# OSSIICBNew.net
KiCad netlist of a schematic drawn in EAGLE
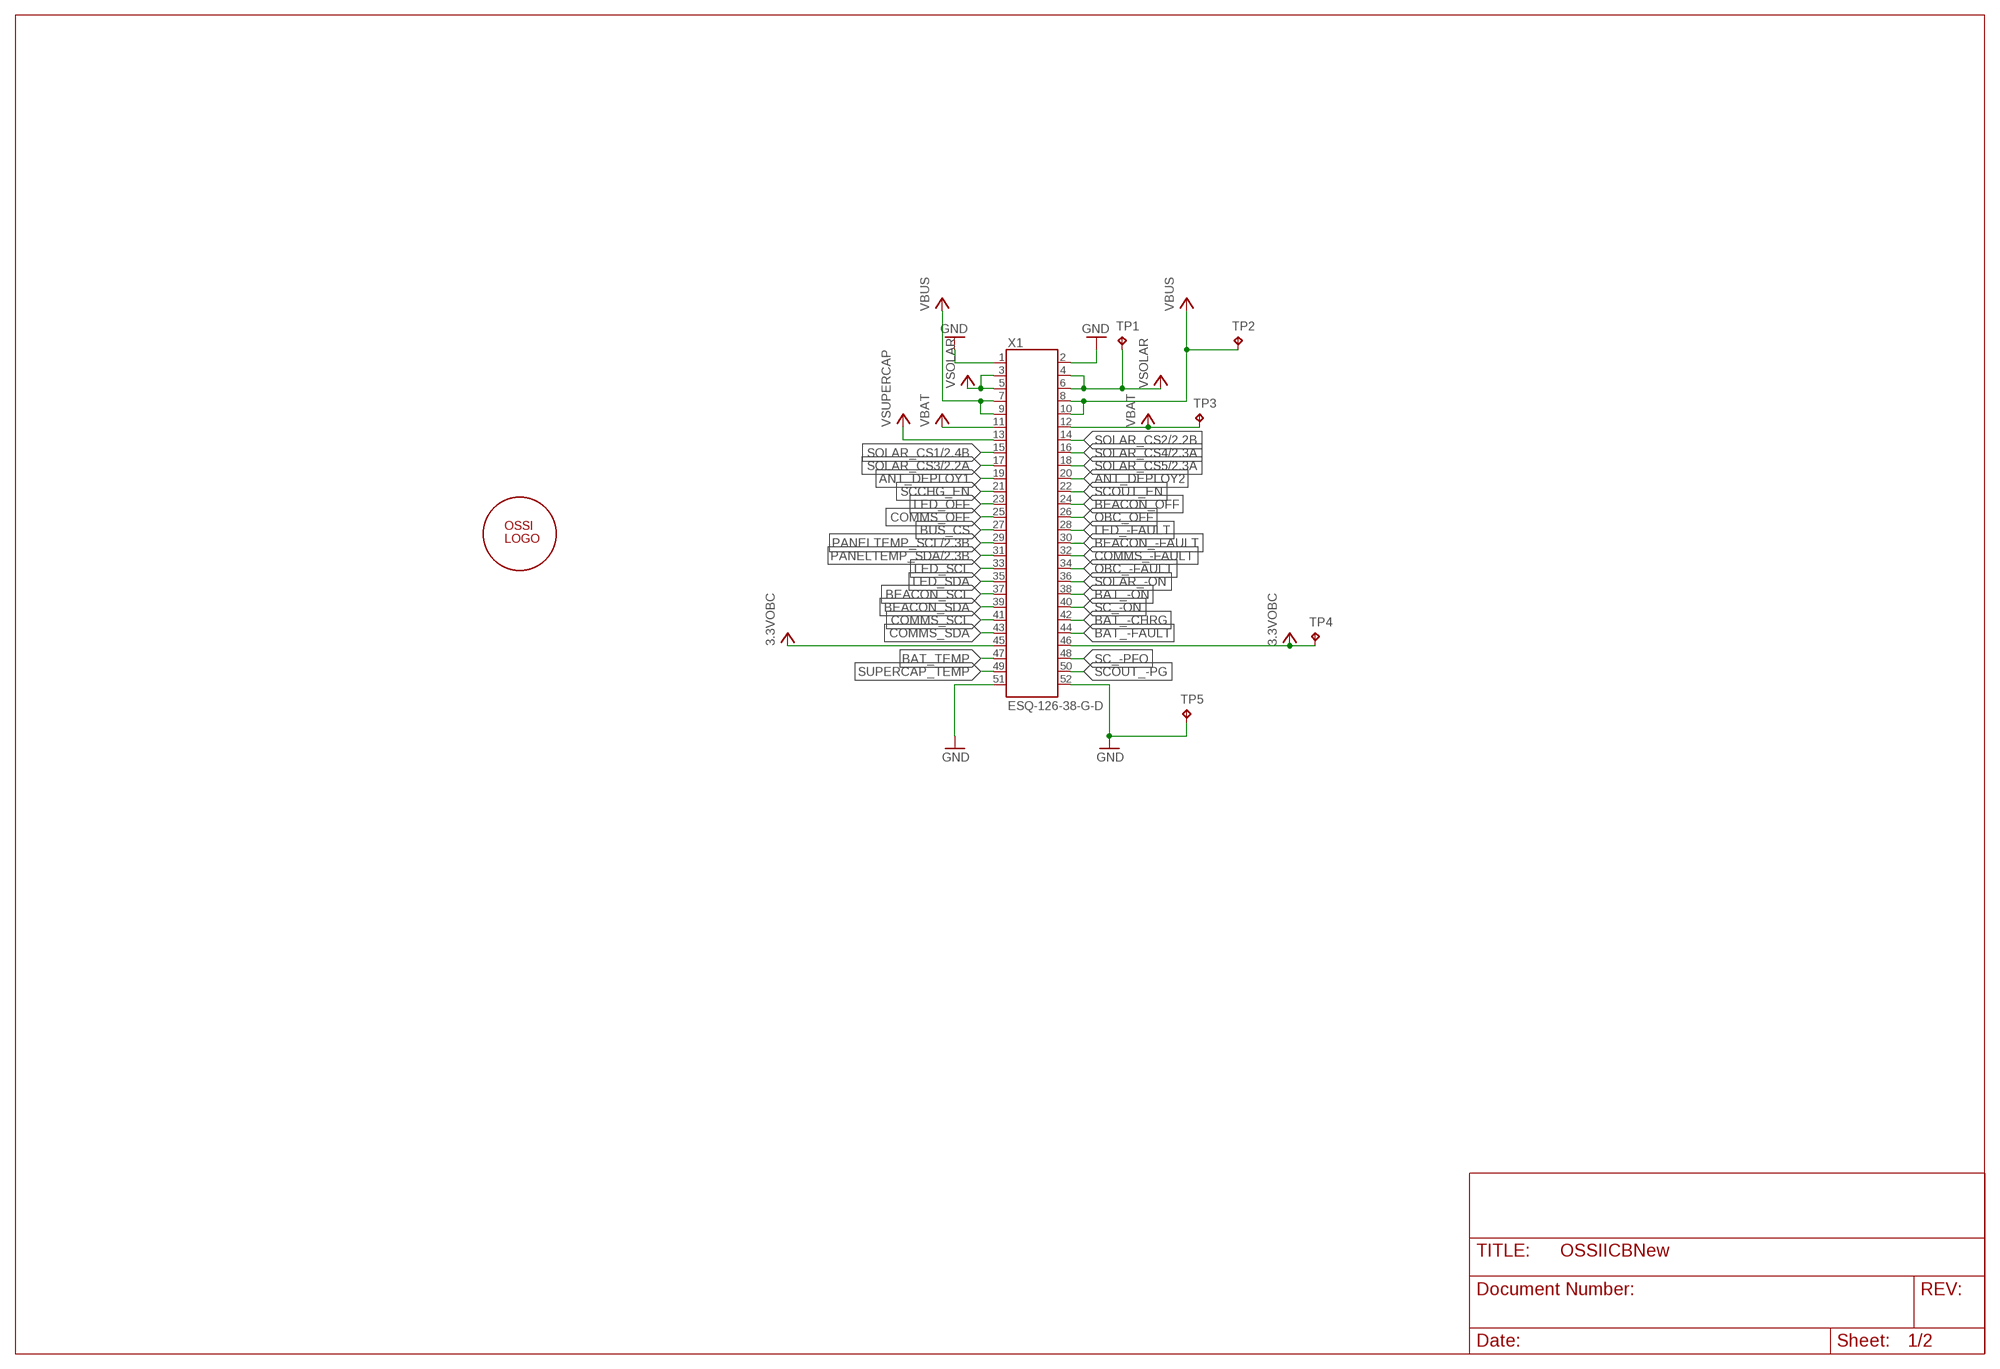
[diagram p0: schematic, sheet 1]
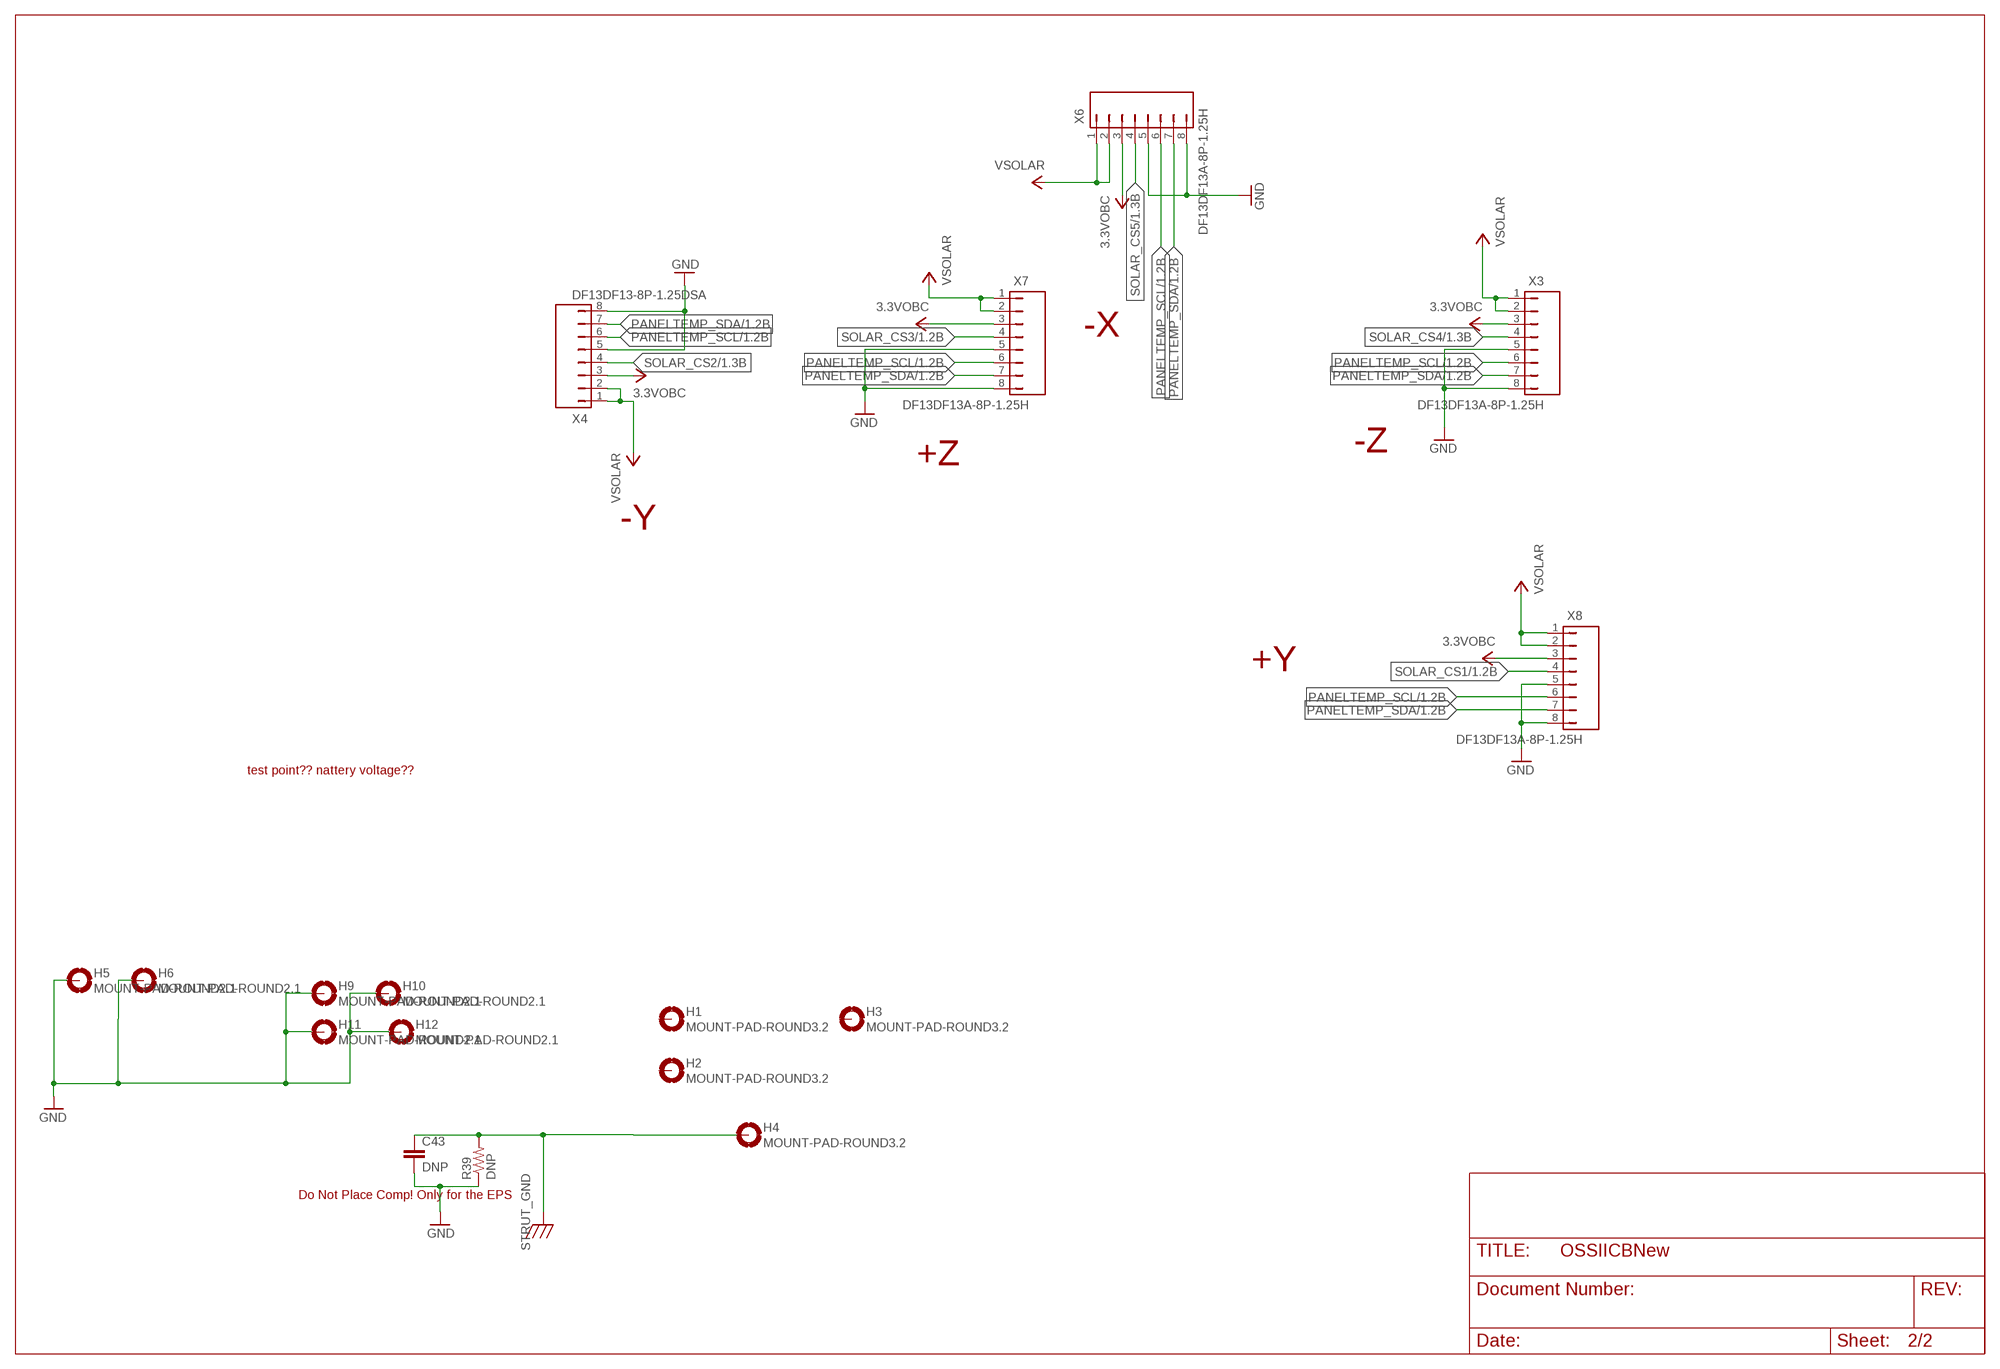
[diagram p1: schematic, sheet 2]

(export (version "E")
  (design (tool "Eeschema 10.0.6"))
  (components
    (comp (ref "TP1")
      (value "TP")
      (footprint "eagle-import:TP-13")
      (libsource (lib "eagle-import") (part "TP"))
    )
    (comp (ref "TP2")
      (value "TP")
      (footprint "eagle-import:TP-13")
      (libsource (lib "eagle-import") (part "TP"))
    )
    (comp (ref "TP3")
      (value "TP")
      (footprint "eagle-import:TP-13")
      (libsource (lib "eagle-import") (part "TP"))
    )
    (comp (ref "TP4")
      (value "TP")
      (footprint "eagle-import:TP-13")
      (libsource (lib "eagle-import") (part "TP"))
    )
    (comp (ref "TP5")
      (value "TP")
      (footprint "eagle-import:TP-13")
      (libsource (lib "eagle-import") (part "TP"))
    )
    (comp (ref "U$1")
      (value "OSSILOGO-10")
      (footprint "eagle-import:OSSILOGO1010")
      (libsource (lib "eagle-import") (part "OSSILOGO-10"))
    )
    (comp (ref "X1")
      (value "ESQ-126-38-G-D")
      (footprint "eagle-import:ESQ-126-XX-X-D")
      (libsource (lib "eagle-import") (part "ESQ-126-38-G-D"))
    )
    (comp (ref "C43")
      (value "DNP")
      (footprint "eagle-import:C0805(2012)")
      (libsource (lib "eagle-import") (part "C0805(2012)"))
    )
    (comp (ref "H1")
      (value "MOUNT-PAD-ROUND3.2")
      (footprint "eagle-import:3.2-PAD-ROUND")
      (libsource (lib "eagle-import") (part "MOUNT-PAD-ROUND3.2"))
    )
    (comp (ref "H2")
      (value "MOUNT-PAD-ROUND3.2")
      (footprint "eagle-import:3.2-PAD-ROUND")
      (libsource (lib "eagle-import") (part "MOUNT-PAD-ROUND3.2"))
    )
    (comp (ref "H3")
      (value "MOUNT-PAD-ROUND3.2")
      (footprint "eagle-import:3.2-PAD-ROUND")
      (libsource (lib "eagle-import") (part "MOUNT-PAD-ROUND3.2"))
    )
    (comp (ref "H4")
      (value "MOUNT-PAD-ROUND3.2")
      (footprint "eagle-import:3.2-PAD-ROUND")
      (libsource (lib "eagle-import") (part "MOUNT-PAD-ROUND3.2"))
    )
    (comp (ref "H5")
      (value "MOUNT-PAD-ROUND2.1")
      (footprint "eagle-import:2.1-PAD-ROUND")
      (libsource (lib "eagle-import") (part "MOUNT-PAD-ROUND2.1"))
    )
    (comp (ref "H6")
      (value "MOUNT-PAD-ROUND2.1")
      (footprint "eagle-import:2.1-PAD-ROUND")
      (libsource (lib "eagle-import") (part "MOUNT-PAD-ROUND2.1"))
    )
    (comp (ref "H9")
      (value "MOUNT-PAD-ROUND2.1")
      (footprint "eagle-import:2.1-PAD-ROUND")
      (libsource (lib "eagle-import") (part "MOUNT-PAD-ROUND2.1"))
    )
    (comp (ref "H10")
      (value "MOUNT-PAD-ROUND2.1")
      (footprint "eagle-import:2.1-PAD-ROUND")
      (libsource (lib "eagle-import") (part "MOUNT-PAD-ROUND2.1"))
    )
    (comp (ref "H11")
      (value "MOUNT-PAD-ROUND2.1")
      (footprint "eagle-import:2.1-PAD-ROUND")
      (libsource (lib "eagle-import") (part "MOUNT-PAD-ROUND2.1"))
    )
    (comp (ref "H12")
      (value "MOUNT-PAD-ROUND2.1")
      (footprint "eagle-import:2.1-PAD-ROUND")
      (libsource (lib "eagle-import") (part "MOUNT-PAD-ROUND2.1"))
    )
    (comp (ref "R39")
      (value "DNP")
      (footprint "eagle-import:WSL1206")
      (libsource (lib "eagle-import") (part "RWSL1206"))
    )
    (comp (ref "X3")
      (value "DF13DF13A-8P-1.25H")
      (footprint "eagle-import:DF13A-8P")
      (libsource (lib "eagle-import") (part "DF13DF13A-8P-1.25H"))
    )
    (comp (ref "X4")
      (value "DF13DF13-8P-1.25DSA")
      (footprint "eagle-import:DF13-8P-1.25DSA")
      (libsource (lib "eagle-import") (part "DF13DF13-8P-1.25DSA"))
    )
    (comp (ref "X6")
      (value "DF13DF13A-8P-1.25H")
      (footprint "eagle-import:DF13A-8P")
      (libsource (lib "eagle-import") (part "DF13DF13A-8P-1.25H"))
    )
    (comp (ref "X7")
      (value "DF13DF13A-8P-1.25H")
      (footprint "eagle-import:DF13A-8P")
      (libsource (lib "eagle-import") (part "DF13DF13A-8P-1.25H"))
    )
    (comp (ref "X8")
      (value "DF13DF13A-8P-1.25H")
      (footprint "eagle-import:DF13A-8P")
      (libsource (lib "eagle-import") (part "DF13DF13A-8P-1.25H"))
    )
  )
  (nets
    (net (code "1") (name "3.3VOBC") (class "Default")
      (node (ref "TP4") (pin "TP") (pinfunction "TP_TP") (pintype "input"))
      (node (ref "X1") (pin "45") (pinfunction "45_45") (pintype "bidirectional"))
      (node (ref "X1") (pin "46") (pinfunction "46_46") (pintype "bidirectional"))
      (node (ref "X3") (pin "3") (pinfunction "3_3") (pintype "passive"))
      (node (ref "X4") (pin "3") (pinfunction "3_3") (pintype "passive"))
      (node (ref "X6") (pin "3") (pinfunction "3_3") (pintype "passive"))
      (node (ref "X7") (pin "3") (pinfunction "3_3") (pintype "passive"))
      (node (ref "X8") (pin "3") (pinfunction "3_3") (pintype "passive"))
    )
    (net (code "2") (name "ANT_DEPLOY1") (class "Default")
      (node (ref "X1") (pin "19") (pinfunction "19_19") (pintype "bidirectional"))
    )
    (net (code "3") (name "ANT_DEPLOY2") (class "Default")
      (node (ref "X1") (pin "20") (pinfunction "20_20") (pintype "bidirectional"))
    )
    (net (code "4") (name "BAT_-CHRG") (class "Default")
      (node (ref "X1") (pin "42") (pinfunction "42_42") (pintype "bidirectional"))
    )
    (net (code "5") (name "BAT_-FAULT") (class "Default")
      (node (ref "X1") (pin "44") (pinfunction "44_44") (pintype "bidirectional"))
    )
    (net (code "6") (name "BAT_-ON") (class "Default")
      (node (ref "X1") (pin "38") (pinfunction "38_38") (pintype "bidirectional"))
    )
    (net (code "7") (name "BAT_TEMP") (class "Default")
      (node (ref "X1") (pin "47") (pinfunction "47_47") (pintype "bidirectional"))
    )
    (net (code "8") (name "BEACON_-FAULT") (class "Default")
      (node (ref "X1") (pin "30") (pinfunction "30_30") (pintype "bidirectional"))
    )
    (net (code "9") (name "BEACON_OFF") (class "Default")
      (node (ref "X1") (pin "24") (pinfunction "24_24") (pintype "bidirectional"))
    )
    (net (code "10") (name "BEACON_SCL") (class "Default")
      (node (ref "X1") (pin "37") (pinfunction "37_37") (pintype "bidirectional"))
    )
    (net (code "11") (name "BEACON_SDA") (class "Default")
      (node (ref "X1") (pin "39") (pinfunction "39_39") (pintype "bidirectional"))
    )
    (net (code "12") (name "BUS_CS") (class "Default")
      (node (ref "X1") (pin "27") (pinfunction "27_27") (pintype "bidirectional"))
    )
    (net (code "13") (name "COMMS_-FAULT") (class "Default")
      (node (ref "X1") (pin "32") (pinfunction "32_32") (pintype "bidirectional"))
    )
    (net (code "14") (name "COMMS_OFF") (class "Default")
      (node (ref "X1") (pin "25") (pinfunction "25_25") (pintype "bidirectional"))
    )
    (net (code "15") (name "COMMS_SCL") (class "Default")
      (node (ref "X1") (pin "41") (pinfunction "41_41") (pintype "bidirectional"))
    )
    (net (code "16") (name "COMMS_SDA") (class "Default")
      (node (ref "X1") (pin "43") (pinfunction "43_43") (pintype "bidirectional"))
    )
    (net (code "17") (name "GND") (class "Default")
      (node (ref "C43") (pin "2") (pinfunction "2_2") (pintype "passive"))
      (node (ref "H10") (pin "B3,2") (pinfunction "MOUNT_B3,2") (pintype "passive"))
      (node (ref "H11") (pin "B3,2") (pinfunction "MOUNT_B3,2") (pintype "passive"))
      (node (ref "H12") (pin "B3,2") (pinfunction "MOUNT_B3,2") (pintype "passive"))
      (node (ref "H5") (pin "B3,2") (pinfunction "MOUNT_B3,2") (pintype "passive"))
      (node (ref "H6") (pin "B3,2") (pinfunction "MOUNT_B3,2") (pintype "passive"))
      (node (ref "H9") (pin "B3,2") (pinfunction "MOUNT_B3,2") (pintype "passive"))
      (node (ref "R39") (pin "P$1") (pinfunction "1_P$1") (pintype "passive"))
      (node (ref "TP5") (pin "TP") (pinfunction "TP_TP") (pintype "input"))
      (node (ref "X1") (pin "1") (pinfunction "1_1") (pintype "bidirectional"))
      (node (ref "X1") (pin "2") (pinfunction "2_2") (pintype "bidirectional"))
      (node (ref "X1") (pin "51") (pinfunction "51_51") (pintype "bidirectional"))
      (node (ref "X1") (pin "52") (pinfunction "52_52") (pintype "bidirectional"))
      (node (ref "X3") (pin "5") (pinfunction "5_5") (pintype "passive"))
      (node (ref "X3") (pin "8") (pinfunction "8_8") (pintype "passive"))
      (node (ref "X4") (pin "5") (pinfunction "5_5") (pintype "passive"))
      (node (ref "X4") (pin "8") (pinfunction "8_8") (pintype "passive"))
      (node (ref "X6") (pin "5") (pinfunction "5_5") (pintype "passive"))
      (node (ref "X6") (pin "8") (pinfunction "8_8") (pintype "passive"))
      (node (ref "X7") (pin "5") (pinfunction "5_5") (pintype "passive"))
      (node (ref "X7") (pin "8") (pinfunction "8_8") (pintype "passive"))
      (node (ref "X8") (pin "5") (pinfunction "5_5") (pintype "passive"))
      (node (ref "X8") (pin "8") (pinfunction "8_8") (pintype "passive"))
    )
    (net (code "18") (name "LED_-FAULT") (class "Default")
      (node (ref "X1") (pin "28") (pinfunction "28_28") (pintype "bidirectional"))
    )
    (net (code "19") (name "LED_OFF") (class "Default")
      (node (ref "X1") (pin "23") (pinfunction "23_23") (pintype "bidirectional"))
    )
    (net (code "20") (name "LED_SCL") (class "Default")
      (node (ref "X1") (pin "33") (pinfunction "33_33") (pintype "bidirectional"))
    )
    (net (code "21") (name "LED_SDA") (class "Default")
      (node (ref "X1") (pin "35") (pinfunction "35_35") (pintype "bidirectional"))
    )
    (net (code "22") (name "OBC_-FAULT") (class "Default")
      (node (ref "X1") (pin "34") (pinfunction "34_34") (pintype "bidirectional"))
    )
    (net (code "23") (name "OBC_OFF") (class "Default")
      (node (ref "X1") (pin "26") (pinfunction "26_26") (pintype "bidirectional"))
    )
    (net (code "24") (name "PANELTEMP_SCL") (class "Default")
      (node (ref "X1") (pin "29") (pinfunction "29_29") (pintype "bidirectional"))
      (node (ref "X3") (pin "6") (pinfunction "6_6") (pintype "passive"))
      (node (ref "X4") (pin "6") (pinfunction "6_6") (pintype "passive"))
      (node (ref "X6") (pin "6") (pinfunction "6_6") (pintype "passive"))
      (node (ref "X7") (pin "6") (pinfunction "6_6") (pintype "passive"))
      (node (ref "X8") (pin "6") (pinfunction "6_6") (pintype "passive"))
    )
    (net (code "25") (name "PANELTEMP_SDA") (class "Default")
      (node (ref "X1") (pin "31") (pinfunction "31_31") (pintype "bidirectional"))
      (node (ref "X3") (pin "7") (pinfunction "7_7") (pintype "passive"))
      (node (ref "X4") (pin "7") (pinfunction "7_7") (pintype "passive"))
      (node (ref "X6") (pin "7") (pinfunction "7_7") (pintype "passive"))
      (node (ref "X7") (pin "7") (pinfunction "7_7") (pintype "passive"))
      (node (ref "X8") (pin "7") (pinfunction "7_7") (pintype "passive"))
    )
    (net (code "26") (name "SCCHG_EN") (class "Default")
      (node (ref "X1") (pin "21") (pinfunction "21_21") (pintype "bidirectional"))
    )
    (net (code "27") (name "SCOUT_-PG") (class "Default")
      (node (ref "X1") (pin "50") (pinfunction "50_50") (pintype "bidirectional"))
    )
    (net (code "28") (name "SCOUT_EN") (class "Default")
      (node (ref "X1") (pin "22") (pinfunction "22_22") (pintype "bidirectional"))
    )
    (net (code "29") (name "SC_-ON") (class "Default")
      (node (ref "X1") (pin "40") (pinfunction "40_40") (pintype "bidirectional"))
    )
    (net (code "30") (name "SC_-PFO") (class "Default")
      (node (ref "X1") (pin "48") (pinfunction "48_48") (pintype "bidirectional"))
    )
    (net (code "31") (name "SOLAR_-ON") (class "Default")
      (node (ref "X1") (pin "36") (pinfunction "36_36") (pintype "bidirectional"))
    )
    (net (code "32") (name "SOLAR_CS1") (class "Default")
      (node (ref "X1") (pin "15") (pinfunction "15_15") (pintype "bidirectional"))
      (node (ref "X8") (pin "4") (pinfunction "4_4") (pintype "passive"))
    )
    (net (code "33") (name "SOLAR_CS2") (class "Default")
      (node (ref "X1") (pin "14") (pinfunction "14_14") (pintype "bidirectional"))
      (node (ref "X4") (pin "4") (pinfunction "4_4") (pintype "passive"))
    )
    (net (code "34") (name "SOLAR_CS3") (class "Default")
      (node (ref "X1") (pin "17") (pinfunction "17_17") (pintype "bidirectional"))
      (node (ref "X7") (pin "4") (pinfunction "4_4") (pintype "passive"))
    )
    (net (code "35") (name "SOLAR_CS4") (class "Default")
      (node (ref "X1") (pin "16") (pinfunction "16_16") (pintype "bidirectional"))
      (node (ref "X3") (pin "4") (pinfunction "4_4") (pintype "passive"))
    )
    (net (code "36") (name "SOLAR_CS5") (class "Default")
      (node (ref "X1") (pin "18") (pinfunction "18_18") (pintype "bidirectional"))
      (node (ref "X6") (pin "4") (pinfunction "4_4") (pintype "passive"))
    )
    (net (code "37") (name "STRUT_GND") (class "Default")
      (node (ref "C43") (pin "1") (pinfunction "1_1") (pintype "passive"))
      (node (ref "H4") (pin "B3,2") (pinfunction "MOUNT_B3,2") (pintype "passive"))
      (node (ref "R39") (pin "P$2") (pinfunction "2_P$2") (pintype "passive"))
    )
    (net (code "38") (name "SUPERCAP_TEMP") (class "Default")
      (node (ref "X1") (pin "49") (pinfunction "49_49") (pintype "bidirectional"))
    )
    (net (code "39") (name "VBAT") (class "Default")
      (node (ref "TP3") (pin "TP") (pinfunction "TP_TP") (pintype "input"))
      (node (ref "X1") (pin "11") (pinfunction "11_11") (pintype "bidirectional"))
      (node (ref "X1") (pin "12") (pinfunction "12_12") (pintype "bidirectional"))
    )
    (net (code "40") (name "VBUS") (class "Default")
      (node (ref "TP2") (pin "TP") (pinfunction "TP_TP") (pintype "input"))
      (node (ref "X1") (pin "10") (pinfunction "10_10") (pintype "bidirectional"))
      (node (ref "X1") (pin "7") (pinfunction "7_7") (pintype "bidirectional"))
      (node (ref "X1") (pin "8") (pinfunction "8_8") (pintype "bidirectional"))
      (node (ref "X1") (pin "9") (pinfunction "9_9") (pintype "bidirectional"))
    )
    (net (code "41") (name "VSOLAR") (class "Default")
      (node (ref "TP1") (pin "TP") (pinfunction "TP_TP") (pintype "input"))
      (node (ref "X1") (pin "3") (pinfunction "3_3") (pintype "bidirectional"))
      (node (ref "X1") (pin "4") (pinfunction "4_4") (pintype "bidirectional"))
      (node (ref "X1") (pin "5") (pinfunction "5_5") (pintype "bidirectional"))
      (node (ref "X1") (pin "6") (pinfunction "6_6") (pintype "bidirectional"))
      (node (ref "X3") (pin "1") (pinfunction "1_1") (pintype "passive"))
      (node (ref "X3") (pin "2") (pinfunction "2_2") (pintype "passive"))
      (node (ref "X4") (pin "1") (pinfunction "1_1") (pintype "passive"))
      (node (ref "X4") (pin "2") (pinfunction "2_2") (pintype "passive"))
      (node (ref "X6") (pin "1") (pinfunction "1_1") (pintype "passive"))
      (node (ref "X6") (pin "2") (pinfunction "2_2") (pintype "passive"))
      (node (ref "X7") (pin "1") (pinfunction "1_1") (pintype "passive"))
      (node (ref "X7") (pin "2") (pinfunction "2_2") (pintype "passive"))
      (node (ref "X8") (pin "1") (pinfunction "1_1") (pintype "passive"))
      (node (ref "X8") (pin "2") (pinfunction "2_2") (pintype "passive"))
    )
    (net (code "42") (name "VSUPERCAP") (class "Default")
      (node (ref "X1") (pin "13") (pinfunction "13_13") (pintype "bidirectional"))
    )
    (net (code "43") (name "unconnected-(H1-MOUNT-PadB3,2)") (class "Default")
      (node (ref "H1") (pin "B3,2") (pinfunction "MOUNT_B3,2") (pintype "passive"))
    )
    (net (code "44") (name "unconnected-(H2-MOUNT-PadB3,2)") (class "Default")
      (node (ref "H2") (pin "B3,2") (pinfunction "MOUNT_B3,2") (pintype "passive"))
    )
    (net (code "45") (name "unconnected-(H3-MOUNT-PadB3,2)") (class "Default")
      (node (ref "H3") (pin "B3,2") (pinfunction "MOUNT_B3,2") (pintype "passive"))
    )
  )
)
